# CommandBoard.net
KiCad netlist of a schematic drawn in Altium Designer
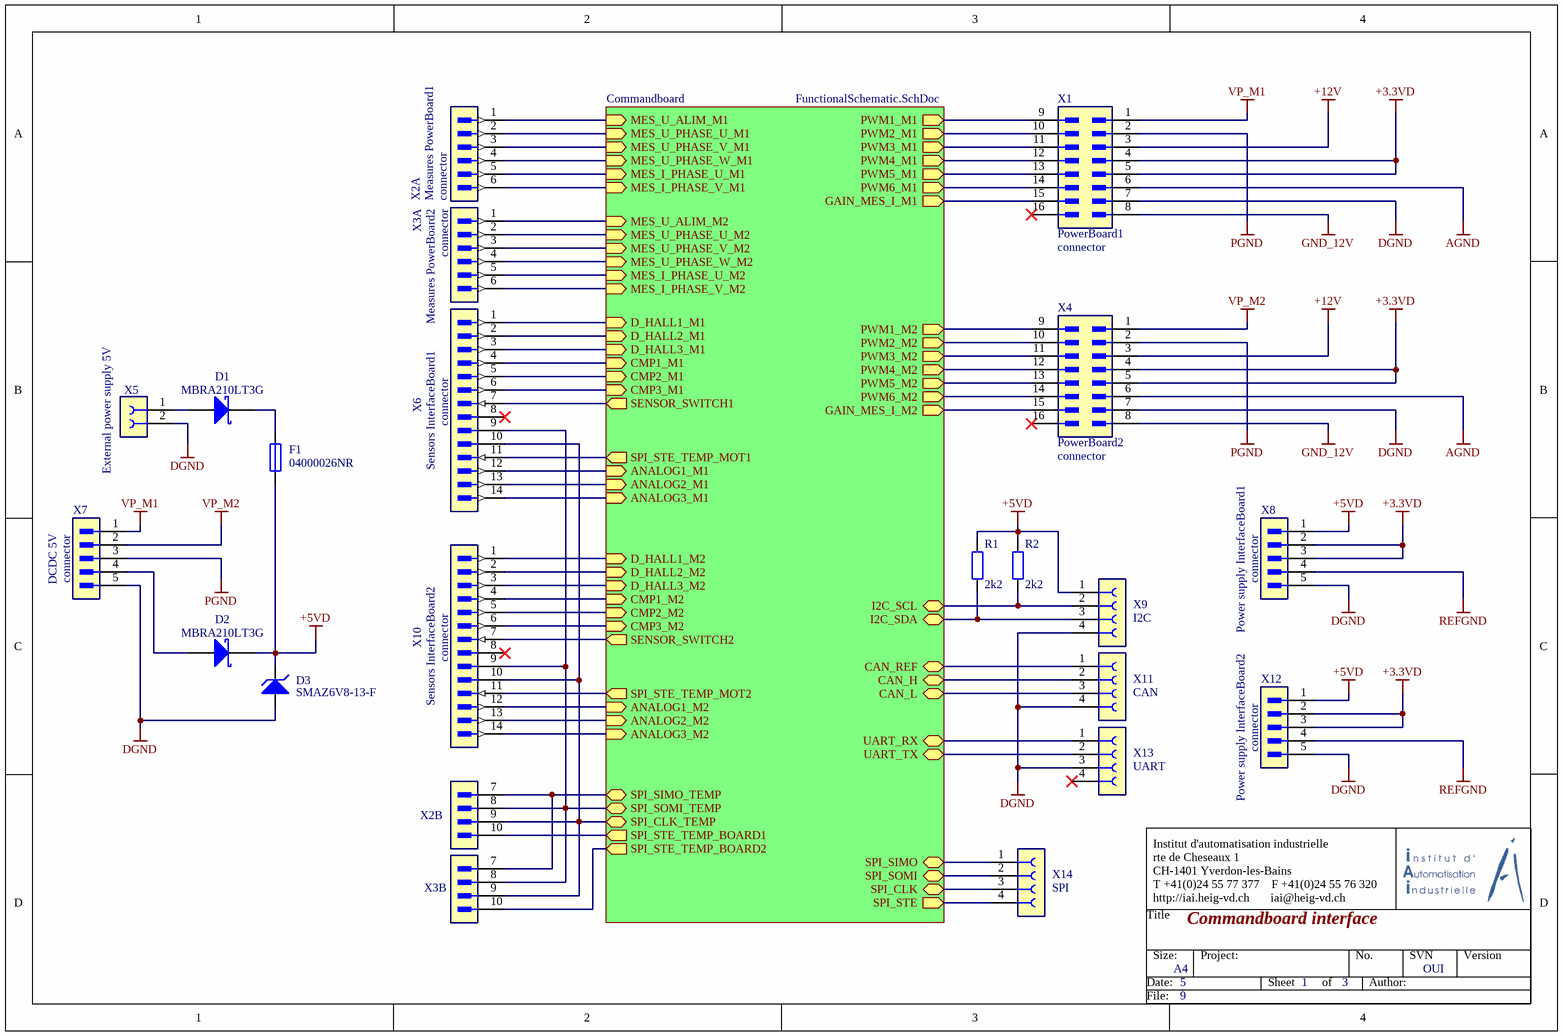
[diagram p0: CommandBoard.SchDoc]

(export (version "E")
  (design (tool "Eeschema 10.0.6"))
  (components
    (comp (ref "D1")
      (value "MBRA210LT3G")
      (footprint "CommandBoard:DIOM4326X22N")
      (description "Diode Schottky 10V 2A Montage en surface SMA")
      (fields (field (name "Comment") "DIODE SCHOTTKY 10V 2A SMA"))
      (libsource (lib "CommandBoard") (part "DIODE SCHOTTKY 10V 2A SMA"))
    )
    (comp (ref "D2")
      (value "MBRA210LT3G")
      (footprint "CommandBoard:DIOM4326X22N")
      (description "Diode Schottky 10V 2A Montage en surface SMA")
      (fields (field (name "Comment") "DIODE SCHOTTKY 10V 2A SMA"))
      (libsource (lib "CommandBoard") (part "DIODE SCHOTTKY 10V 2A SMA"))
    )
    (comp (ref "D3")
      (value "SMAZ6V8-13-F")
      (footprint "CommandBoard:DIOM4326X22N")
      (description "Diodes - Zener 6,8V 1W ±5% Montage en surface SMA")
      (fields (field (name "Comment") "DIODE ZENER 6.8V 1W SMA"))
      (libsource (lib "CommandBoard") (part "DIODE ZENER 6.8V 1W SMA"))
    )
    (comp (ref "F1")
      (value "04000026NR")
      (footprint "CommandBoard:FUSEC1508X06N")
      (fields (field (name "Comment") "FUSE 1.5A 5V FAST 0603 SMD"))
      (libsource (lib "CommandBoard") (part "FUSE 1.5A 5V FAST 0603 SMD"))
    )
    (comp (ref "R1")
      (value "2k2")
      (footprint "CommandBoard:RESC1508X04N")
      (description "2,2 kOhms ±1% 0,1W, 1/10W Pavé résistif 0603 (1608 métrique) AutomobileAEC-Q200 Couche épaisse")
      (fields (field (name "Comment") "RES SMD 2K2 0603"))
      (libsource (lib "CommandBoard") (part "RES SMD 2K2 OHM 1% 1/10W 0603"))
    )
    (comp (ref "R2")
      (value "2k2")
      (footprint "CommandBoard:RESC1508X04N")
      (description "2,2 kOhms ±1% 0,1W, 1/10W Pavé résistif 0603 (1608 métrique) AutomobileAEC-Q200 Couche épaisse")
      (fields (field (name "Comment") "RES SMD 2K2 0603"))
      (libsource (lib "CommandBoard") (part "RES SMD 2K2 OHM 1% 1/10W 0603"))
    )
    (comp (ref "X1")
      (value "CONNECT SMD 16pos 180°")
      (footprint "CommandBoard:62101621021")
      (fields (field (name "USE") "PowerBoard1") (field (name "SYSTEM") "connector"))
      (libsource (lib "CommandBoard") (part "CONNECT SMD 16pos 2row 180° 1.27mm"))
    )
    (comp (ref "X2")
      (value "CONNECT SMD 10pos 180°")
      (footprint "CommandBoard:62101021021")
      (fields (field (name "USE") "Measures PowerBoard1") (field (name "SYSTEM") "connector"))
      (libsource (lib "CommandBoard") (part "CONNECT SMD 10pos 180° 1.27mm"))
    )
    (comp (ref "X3")
      (value "CONNECT SMD 10pos 180°")
      (footprint "CommandBoard:62101021021")
      (fields (field (name "USE") "Measures PowerBoard2") (field (name "SYSTEM") "connector"))
      (libsource (lib "CommandBoard") (part "CONNECT SMD 10pos 180° 1.27mm"))
    )
    (comp (ref "X4")
      (value "CONNECT SMD 16pos 180°")
      (footprint "CommandBoard:62101621021")
      (fields (field (name "USE") "PowerBoard2") (field (name "SYSTEM") "connector"))
      (libsource (lib "CommandBoard") (part "CONNECT SMD 16pos 2row 180° 1.27mm"))
    )
    (comp (ref "X5")
      (value "CONNECT 2pos 90°")
      (footprint "CommandBoard:WR-TBL322 3.81mm 2p")
      (fields (field (name "USE") "External power supply 5V"))
      (libsource (lib "CommandBoard") (part "CONNECT 2pos 90° 3.81mm F"))
    )
    (comp (ref "X6")
      (value "CONNECT SMD 16pos 180°")
      (footprint "62101421021")
      (fields (field (name "USE") "Sensors InterfaceBoard1") (field (name "SYSTEM") "connector"))
      (libsource (lib "CommandBoard") (part "CONNECT SMD 14pos 180° 1.27mm"))
    )
    (comp (ref "X7")
      (value "CONNECT SMD 5pos 180°")
      (footprint "CommandBoard:62000611121")
      (fields (field (name "USE") "DCDC 5V") (field (name "SYSTEM") "connector"))
      (libsource (lib "CommandBoard") (part "CONNECT SMD 5pos 180° 2mm"))
    )
    (comp (ref "X8")
      (value "CONNECT SMD 5pos 180°")
      (footprint "CommandBoard:62000611121")
      (fields (field (name "USE") "Power supply InterfaceBoard1") (field (name "SYSTEM") "connector"))
      (libsource (lib "CommandBoard") (part "CONNECT SMD 5pos 180° 2mm"))
    )
    (comp (ref "X9")
      (value "CONNECT SMD 4pos 180°")
      (footprint "CommandBoard:TE_7-215079-4")
      (description "Connecteur, embase Montage en surface 4 positions 0,100 po (2,54mm)")
      (fields (field (name "USE") "I2C"))
      (libsource (lib "CommandBoard") (part "CONNECT SMD 4pos 180° 2.54mm F"))
    )
    (comp (ref "X10")
      (value "CONNECT SMD 16pos 180°")
      (footprint "62101421021")
      (fields (field (name "USE") "Sensors InterfaceBoard2") (field (name "SYSTEM") "connector"))
      (libsource (lib "CommandBoard") (part "CONNECT SMD 14pos 180° 1.27mm"))
    )
    (comp (ref "X11")
      (value "CONNECT SMD 4pos 180°")
      (footprint "CommandBoard:TE_7-215079-4")
      (description "Connecteur, embase Montage en surface 4 positions 0,100 po (2,54mm)")
      (fields (field (name "USE") "CAN"))
      (libsource (lib "CommandBoard") (part "CONNECT SMD 4pos 180° 2.54mm F"))
    )
    (comp (ref "X12")
      (value "CONNECT SMD 5pos 180°")
      (footprint "CommandBoard:62000611121")
      (fields (field (name "USE") "Power supply InterfaceBoard2") (field (name "SYSTEM") "connector"))
      (libsource (lib "CommandBoard") (part "CONNECT SMD 5pos 180° 2mm"))
    )
    (comp (ref "X13")
      (value "CONNECT SMD 4pos 180°")
      (footprint "CommandBoard:TE_7-215079-4")
      (description "Connecteur, embase Montage en surface 4 positions 0,100 po (2,54mm)")
      (fields (field (name "USE") "UART"))
      (libsource (lib "CommandBoard") (part "CONNECT SMD 4pos 180° 2.54mm F"))
    )
    (comp (ref "X14")
      (value "CONNECT SMD 4pos 180°")
      (footprint "CommandBoard:TE_7-215079-4")
      (description "Connecteur, embase Montage en surface 4 positions 0,100 po (2,54mm)")
      (fields (field (name "USE") "SPI"))
      (libsource (lib "CommandBoard") (part "CONNECT SMD 4pos 180° 2.54mm F"))
    )
  )
  (nets
    (net (code "1") (name "+3.3VD") (class "Default")
      (node (ref "X1") (pin "4") (pinfunction "4_4") (pintype "passive"))
      (node (ref "X1") (pin "5") (pinfunction "5_5") (pintype "passive"))
      (node (ref "X12") (pin "2") (pinfunction "2_2") (pintype "passive"))
      (node (ref "X12") (pin "3") (pinfunction "3_3") (pintype "passive"))
      (node (ref "X4") (pin "4") (pinfunction "4_4") (pintype "passive"))
      (node (ref "X4") (pin "5") (pinfunction "5_5") (pintype "passive"))
      (node (ref "X8") (pin "2") (pinfunction "2_2") (pintype "passive"))
      (node (ref "X8") (pin "3") (pinfunction "3_3") (pintype "passive"))
    )
    (net (code "2") (name "+5VD") (class "Default")
      (node (ref "D2") (pin "2") (pinfunction "K_2") (pintype "passive"))
      (node (ref "D3") (pin "2") (pinfunction "K_2") (pintype "passive"))
      (node (ref "F1") (pin "1") (pinfunction "1_1") (pintype "passive"))
      (node (ref "R1") (pin "2") (pinfunction "2_2") (pintype "passive"))
      (node (ref "R2") (pin "2") (pinfunction "2_2") (pintype "passive"))
      (node (ref "X12") (pin "1") (pinfunction "1_1") (pintype "passive"))
      (node (ref "X8") (pin "1") (pinfunction "1_1") (pintype "passive"))
      (node (ref "X9") (pin "1") (pinfunction "1_1") (pintype "passive"))
    )
    (net (code "3") (name "+12V") (class "Default")
      (node (ref "X1") (pin "3") (pinfunction "3_3") (pintype "passive"))
      (node (ref "X4") (pin "3") (pinfunction "3_3") (pintype "passive"))
    )
    (net (code "4") (name "/ANALOG1_M1") (class "Default")
      (node (ref "X6") (pin "12") (pinfunction "12_12") (pintype "output"))
    )
    (net (code "5") (name "/ANALOG1_M2") (class "Default")
      (node (ref "X10") (pin "12") (pinfunction "12_12") (pintype "output"))
    )
    (net (code "6") (name "/ANALOG2_M1") (class "Default")
      (node (ref "X6") (pin "13") (pinfunction "13_13") (pintype "output"))
    )
    (net (code "7") (name "/ANALOG2_M2") (class "Default")
      (node (ref "X10") (pin "13") (pinfunction "13_13") (pintype "output"))
    )
    (net (code "8") (name "/ANALOG3_M1") (class "Default")
      (node (ref "X6") (pin "14") (pinfunction "14_14") (pintype "output"))
    )
    (net (code "9") (name "/ANALOG3_M2") (class "Default")
      (node (ref "X10") (pin "14") (pinfunction "14_14") (pintype "output"))
    )
    (net (code "10") (name "/CAN_H") (class "Default")
      (node (ref "X11") (pin "2") (pinfunction "2_2") (pintype "passive"))
    )
    (net (code "11") (name "/CAN_L") (class "Default")
      (node (ref "X11") (pin "3") (pinfunction "3_3") (pintype "passive"))
    )
    (net (code "12") (name "/CAN_REF") (class "Default")
      (node (ref "X11") (pin "1") (pinfunction "1_1") (pintype "passive"))
    )
    (net (code "13") (name "/CMP1_M1") (class "Default")
      (node (ref "X6") (pin "4") (pinfunction "4_4") (pintype "output"))
    )
    (net (code "14") (name "/CMP1_M2") (class "Default")
      (node (ref "X10") (pin "4") (pinfunction "4_4") (pintype "output"))
    )
    (net (code "15") (name "/CMP2_M1") (class "Default")
      (node (ref "X6") (pin "5") (pinfunction "5_5") (pintype "output"))
    )
    (net (code "16") (name "/CMP2_M2") (class "Default")
      (node (ref "X10") (pin "5") (pinfunction "5_5") (pintype "output"))
    )
    (net (code "17") (name "/CMP3_M1") (class "Default")
      (node (ref "X6") (pin "6") (pinfunction "6_6") (pintype "output"))
    )
    (net (code "18") (name "/CMP3_M2") (class "Default")
      (node (ref "X10") (pin "6") (pinfunction "6_6") (pintype "output"))
    )
    (net (code "19") (name "/D_HALL1_M1") (class "Default")
      (node (ref "X6") (pin "1") (pinfunction "1_1") (pintype "output"))
    )
    (net (code "20") (name "/D_HALL1_M2") (class "Default")
      (node (ref "X10") (pin "1") (pinfunction "1_1") (pintype "output"))
    )
    (net (code "21") (name "/D_HALL2_M1") (class "Default")
      (node (ref "X6") (pin "2") (pinfunction "2_2") (pintype "output"))
    )
    (net (code "22") (name "/D_HALL2_M2") (class "Default")
      (node (ref "X10") (pin "2") (pinfunction "2_2") (pintype "output"))
    )
    (net (code "23") (name "/D_HALL3_M1") (class "Default")
      (node (ref "X6") (pin "3") (pinfunction "3_3") (pintype "output"))
    )
    (net (code "24") (name "/D_HALL3_M2") (class "Default")
      (node (ref "X10") (pin "3") (pinfunction "3_3") (pintype "output"))
    )
    (net (code "25") (name "/GAIN_MES_I_M1") (class "Default")
      (node (ref "X1") (pin "15") (pinfunction "15_15") (pintype "passive"))
    )
    (net (code "26") (name "/GAIN_MES_I_M2") (class "Default")
      (node (ref "X4") (pin "15") (pinfunction "15_15") (pintype "passive"))
    )
    (net (code "27") (name "/I2C_SCL") (class "Default")
      (node (ref "R2") (pin "1") (pinfunction "1_1") (pintype "passive"))
      (node (ref "X9") (pin "2") (pinfunction "2_2") (pintype "passive"))
    )
    (net (code "28") (name "/I2C_SDA") (class "Default")
      (node (ref "R1") (pin "1") (pinfunction "1_1") (pintype "passive"))
      (node (ref "X9") (pin "3") (pinfunction "3_3") (pintype "passive"))
    )
    (net (code "29") (name "/MES_I_PHASE_U_M1") (class "Default")
      (node (ref "X2") (pin "5") (pinfunction "5_5") (pintype "output"))
    )
    (net (code "30") (name "/MES_I_PHASE_U_M2") (class "Default")
      (node (ref "X3") (pin "5") (pinfunction "5_5") (pintype "output"))
    )
    (net (code "31") (name "/MES_I_PHASE_V_M1") (class "Default")
      (node (ref "X2") (pin "6") (pinfunction "6_6") (pintype "output"))
    )
    (net (code "32") (name "/MES_I_PHASE_V_M2") (class "Default")
      (node (ref "X3") (pin "6") (pinfunction "6_6") (pintype "output"))
    )
    (net (code "33") (name "/MES_U_ALIM_M1") (class "Default")
      (node (ref "X2") (pin "1") (pinfunction "1_1") (pintype "output"))
    )
    (net (code "34") (name "/MES_U_ALIM_M2") (class "Default")
      (node (ref "X3") (pin "1") (pinfunction "1_1") (pintype "output"))
    )
    (net (code "35") (name "/MES_U_PHASE_U_M1") (class "Default")
      (node (ref "X2") (pin "2") (pinfunction "2_2") (pintype "output"))
    )
    (net (code "36") (name "/MES_U_PHASE_U_M2") (class "Default")
      (node (ref "X3") (pin "2") (pinfunction "2_2") (pintype "output"))
    )
    (net (code "37") (name "/MES_U_PHASE_V_M1") (class "Default")
      (node (ref "X2") (pin "3") (pinfunction "3_3") (pintype "output"))
    )
    (net (code "38") (name "/MES_U_PHASE_V_M2") (class "Default")
      (node (ref "X3") (pin "3") (pinfunction "3_3") (pintype "output"))
    )
    (net (code "39") (name "/MES_U_PHASE_W_M1") (class "Default")
      (node (ref "X2") (pin "4") (pinfunction "4_4") (pintype "output"))
    )
    (net (code "40") (name "/MES_U_PHASE_W_M2") (class "Default")
      (node (ref "X3") (pin "4") (pinfunction "4_4") (pintype "output"))
    )
    (net (code "41") (name "/PWM1_M1") (class "Default")
      (node (ref "X1") (pin "9") (pinfunction "9_9") (pintype "passive"))
    )
    (net (code "42") (name "/PWM1_M2") (class "Default")
      (node (ref "X4") (pin "9") (pinfunction "9_9") (pintype "passive"))
    )
    (net (code "43") (name "/PWM2_M1") (class "Default")
      (node (ref "X1") (pin "10") (pinfunction "10_10") (pintype "passive"))
    )
    (net (code "44") (name "/PWM2_M2") (class "Default")
      (node (ref "X4") (pin "10") (pinfunction "10_10") (pintype "passive"))
    )
    (net (code "45") (name "/PWM3_M1") (class "Default")
      (node (ref "X1") (pin "11") (pinfunction "11_11") (pintype "passive"))
    )
    (net (code "46") (name "/PWM3_M2") (class "Default")
      (node (ref "X4") (pin "11") (pinfunction "11_11") (pintype "passive"))
    )
    (net (code "47") (name "/PWM4_M1") (class "Default")
      (node (ref "X1") (pin "12") (pinfunction "12_12") (pintype "passive"))
    )
    (net (code "48") (name "/PWM4_M2") (class "Default")
      (node (ref "X4") (pin "12") (pinfunction "12_12") (pintype "passive"))
    )
    (net (code "49") (name "/PWM5_M1") (class "Default")
      (node (ref "X1") (pin "13") (pinfunction "13_13") (pintype "passive"))
    )
    (net (code "50") (name "/PWM5_M2") (class "Default")
      (node (ref "X4") (pin "13") (pinfunction "13_13") (pintype "passive"))
    )
    (net (code "51") (name "/PWM6_M1") (class "Default")
      (node (ref "X1") (pin "14") (pinfunction "14_14") (pintype "passive"))
    )
    (net (code "52") (name "/PWM6_M2") (class "Default")
      (node (ref "X4") (pin "14") (pinfunction "14_14") (pintype "passive"))
    )
    (net (code "53") (name "/SENSOR_SWITCH1") (class "Default")
      (node (ref "X6") (pin "7") (pinfunction "7_7") (pintype "input"))
    )
    (net (code "54") (name "/SENSOR_SWITCH2") (class "Default")
      (node (ref "X10") (pin "7") (pinfunction "7_7") (pintype "input"))
    )
    (net (code "55") (name "/SPI_CLK") (class "Default")
      (node (ref "X14") (pin "3") (pinfunction "3_3") (pintype "passive"))
    )
    (net (code "56") (name "/SPI_CLK_TEMP") (class "Default")
      (node (ref "X10") (pin "10") (pinfunction "10_10") (pintype "passive"))
      (node (ref "X2") (pin "9") (pinfunction "9_9") (pintype "passive"))
      (node (ref "X3") (pin "9") (pinfunction "9_9") (pintype "passive"))
      (node (ref "X6") (pin "10") (pinfunction "10_10") (pintype "passive"))
    )
    (net (code "57") (name "/SPI_SIMO") (class "Default")
      (node (ref "X14") (pin "1") (pinfunction "1_1") (pintype "passive"))
    )
    (net (code "58") (name "/SPI_SIMO_TEMP") (class "Default")
      (node (ref "X2") (pin "7") (pinfunction "7_7") (pintype "passive"))
      (node (ref "X3") (pin "7") (pinfunction "7_7") (pintype "passive"))
    )
    (net (code "59") (name "/SPI_SOMI") (class "Default")
      (node (ref "X14") (pin "2") (pinfunction "2_2") (pintype "passive"))
    )
    (net (code "60") (name "/SPI_SOMI_TEMP") (class "Default")
      (node (ref "X10") (pin "9") (pinfunction "9_9") (pintype "passive"))
      (node (ref "X2") (pin "8") (pinfunction "8_8") (pintype "passive"))
      (node (ref "X3") (pin "8") (pinfunction "8_8") (pintype "passive"))
      (node (ref "X6") (pin "9") (pinfunction "9_9") (pintype "passive"))
    )
    (net (code "61") (name "/SPI_STE") (class "Default")
      (node (ref "X14") (pin "4") (pinfunction "4_4") (pintype "passive"))
    )
    (net (code "62") (name "/SPI_STE_TEMP_BOARD1") (class "Default")
      (node (ref "X2") (pin "10") (pinfunction "10_10") (pintype "passive"))
    )
    (net (code "63") (name "/SPI_STE_TEMP_BOARD2") (class "Default")
      (node (ref "X3") (pin "10") (pinfunction "10_10") (pintype "passive"))
    )
    (net (code "64") (name "/SPI_STE_TEMP_MOT1") (class "Default")
      (node (ref "X6") (pin "11") (pinfunction "11_11") (pintype "input"))
    )
    (net (code "65") (name "/SPI_STE_TEMP_MOT2") (class "Default")
      (node (ref "X10") (pin "11") (pinfunction "11_11") (pintype "input"))
    )
    (net (code "66") (name "/UART_RX") (class "Default")
      (node (ref "X13") (pin "1") (pinfunction "1_1") (pintype "passive"))
    )
    (net (code "67") (name "/UART_TX") (class "Default")
      (node (ref "X13") (pin "2") (pinfunction "2_2") (pintype "passive"))
    )
    (net (code "68") (name "AGND") (class "Default")
      (node (ref "X1") (pin "6") (pinfunction "6_6") (pintype "passive"))
      (node (ref "X4") (pin "6") (pinfunction "6_6") (pintype "passive"))
    )
    (net (code "69") (name "DGND") (class "Default")
      (node (ref "D3") (pin "1") (pinfunction "A_1") (pintype "passive"))
      (node (ref "X1") (pin "7") (pinfunction "7_7") (pintype "passive"))
      (node (ref "X11") (pin "4") (pinfunction "4_4") (pintype "passive"))
      (node (ref "X12") (pin "5") (pinfunction "5_5") (pintype "passive"))
      (node (ref "X13") (pin "3") (pinfunction "3_3") (pintype "passive"))
      (node (ref "X4") (pin "7") (pinfunction "7_7") (pintype "passive"))
      (node (ref "X5") (pin "2") (pinfunction "2_2") (pintype "passive"))
      (node (ref "X7") (pin "5") (pinfunction "5_5") (pintype "passive"))
      (node (ref "X8") (pin "5") (pinfunction "5_5") (pintype "passive"))
      (node (ref "X9") (pin "4") (pinfunction "4_4") (pintype "passive"))
    )
    (net (code "70") (name "GND_12V") (class "Default")
      (node (ref "X1") (pin "8") (pinfunction "8_8") (pintype "passive"))
      (node (ref "X4") (pin "8") (pinfunction "8_8") (pintype "passive"))
    )
    (net (code "71") (name "Net-(D1-A)") (class "Default")
      (node (ref "D1") (pin "1") (pinfunction "A_1") (pintype "passive"))
      (node (ref "X5") (pin "1") (pinfunction "1_1") (pintype "passive"))
    )
    (net (code "72") (name "Net-(D1-K)") (class "Default")
      (node (ref "D1") (pin "2") (pinfunction "K_2") (pintype "passive"))
      (node (ref "F1") (pin "2") (pinfunction "2_2") (pintype "passive"))
    )
    (net (code "73") (name "Net-(D2-A)") (class "Default")
      (node (ref "D2") (pin "1") (pinfunction "A_1") (pintype "passive"))
      (node (ref "X7") (pin "4") (pinfunction "4_4") (pintype "passive"))
    )
    (net (code "74") (name "PGND") (class "Default")
      (node (ref "X1") (pin "2") (pinfunction "2_2") (pintype "passive"))
      (node (ref "X4") (pin "2") (pinfunction "2_2") (pintype "passive"))
      (node (ref "X7") (pin "3") (pinfunction "3_3") (pintype "passive"))
    )
    (net (code "75") (name "REFGND") (class "Default")
      (node (ref "X12") (pin "4") (pinfunction "4_4") (pintype "passive"))
      (node (ref "X8") (pin "4") (pinfunction "4_4") (pintype "passive"))
    )
    (net (code "76") (name "VP_M1") (class "Default")
      (node (ref "X1") (pin "1") (pinfunction "1_1") (pintype "passive"))
      (node (ref "X7") (pin "1") (pinfunction "1_1") (pintype "passive"))
    )
    (net (code "77") (name "VP_M2") (class "Default")
      (node (ref "X4") (pin "1") (pinfunction "1_1") (pintype "passive"))
      (node (ref "X7") (pin "2") (pinfunction "2_2") (pintype "passive"))
    )
    (net (code "78") (name "unconnected-(X1-Pad16)") (class "Default")
      (node (ref "X1") (pin "16") (pinfunction "16_16") (pintype "passive+no_connect"))
    )
    (net (code "79") (name "unconnected-(X4-Pad16)") (class "Default")
      (node (ref "X4") (pin "16") (pinfunction "16_16") (pintype "passive+no_connect"))
    )
    (net (code "80") (name "unconnected-(X6-Pad8)") (class "Default")
      (node (ref "X6") (pin "8") (pinfunction "8_8") (pintype "passive+no_connect"))
    )
    (net (code "81") (name "unconnected-(X10-Pad8)") (class "Default")
      (node (ref "X10") (pin "8") (pinfunction "8_8") (pintype "passive+no_connect"))
    )
    (net (code "82") (name "unconnected-(X13-Pad4)") (class "Default")
      (node (ref "X13") (pin "4") (pinfunction "4_4") (pintype "passive+no_connect"))
    )
  )
)
